# boat_2.net
KiCad netlist of a schematic drawn in EasyEDA Pro
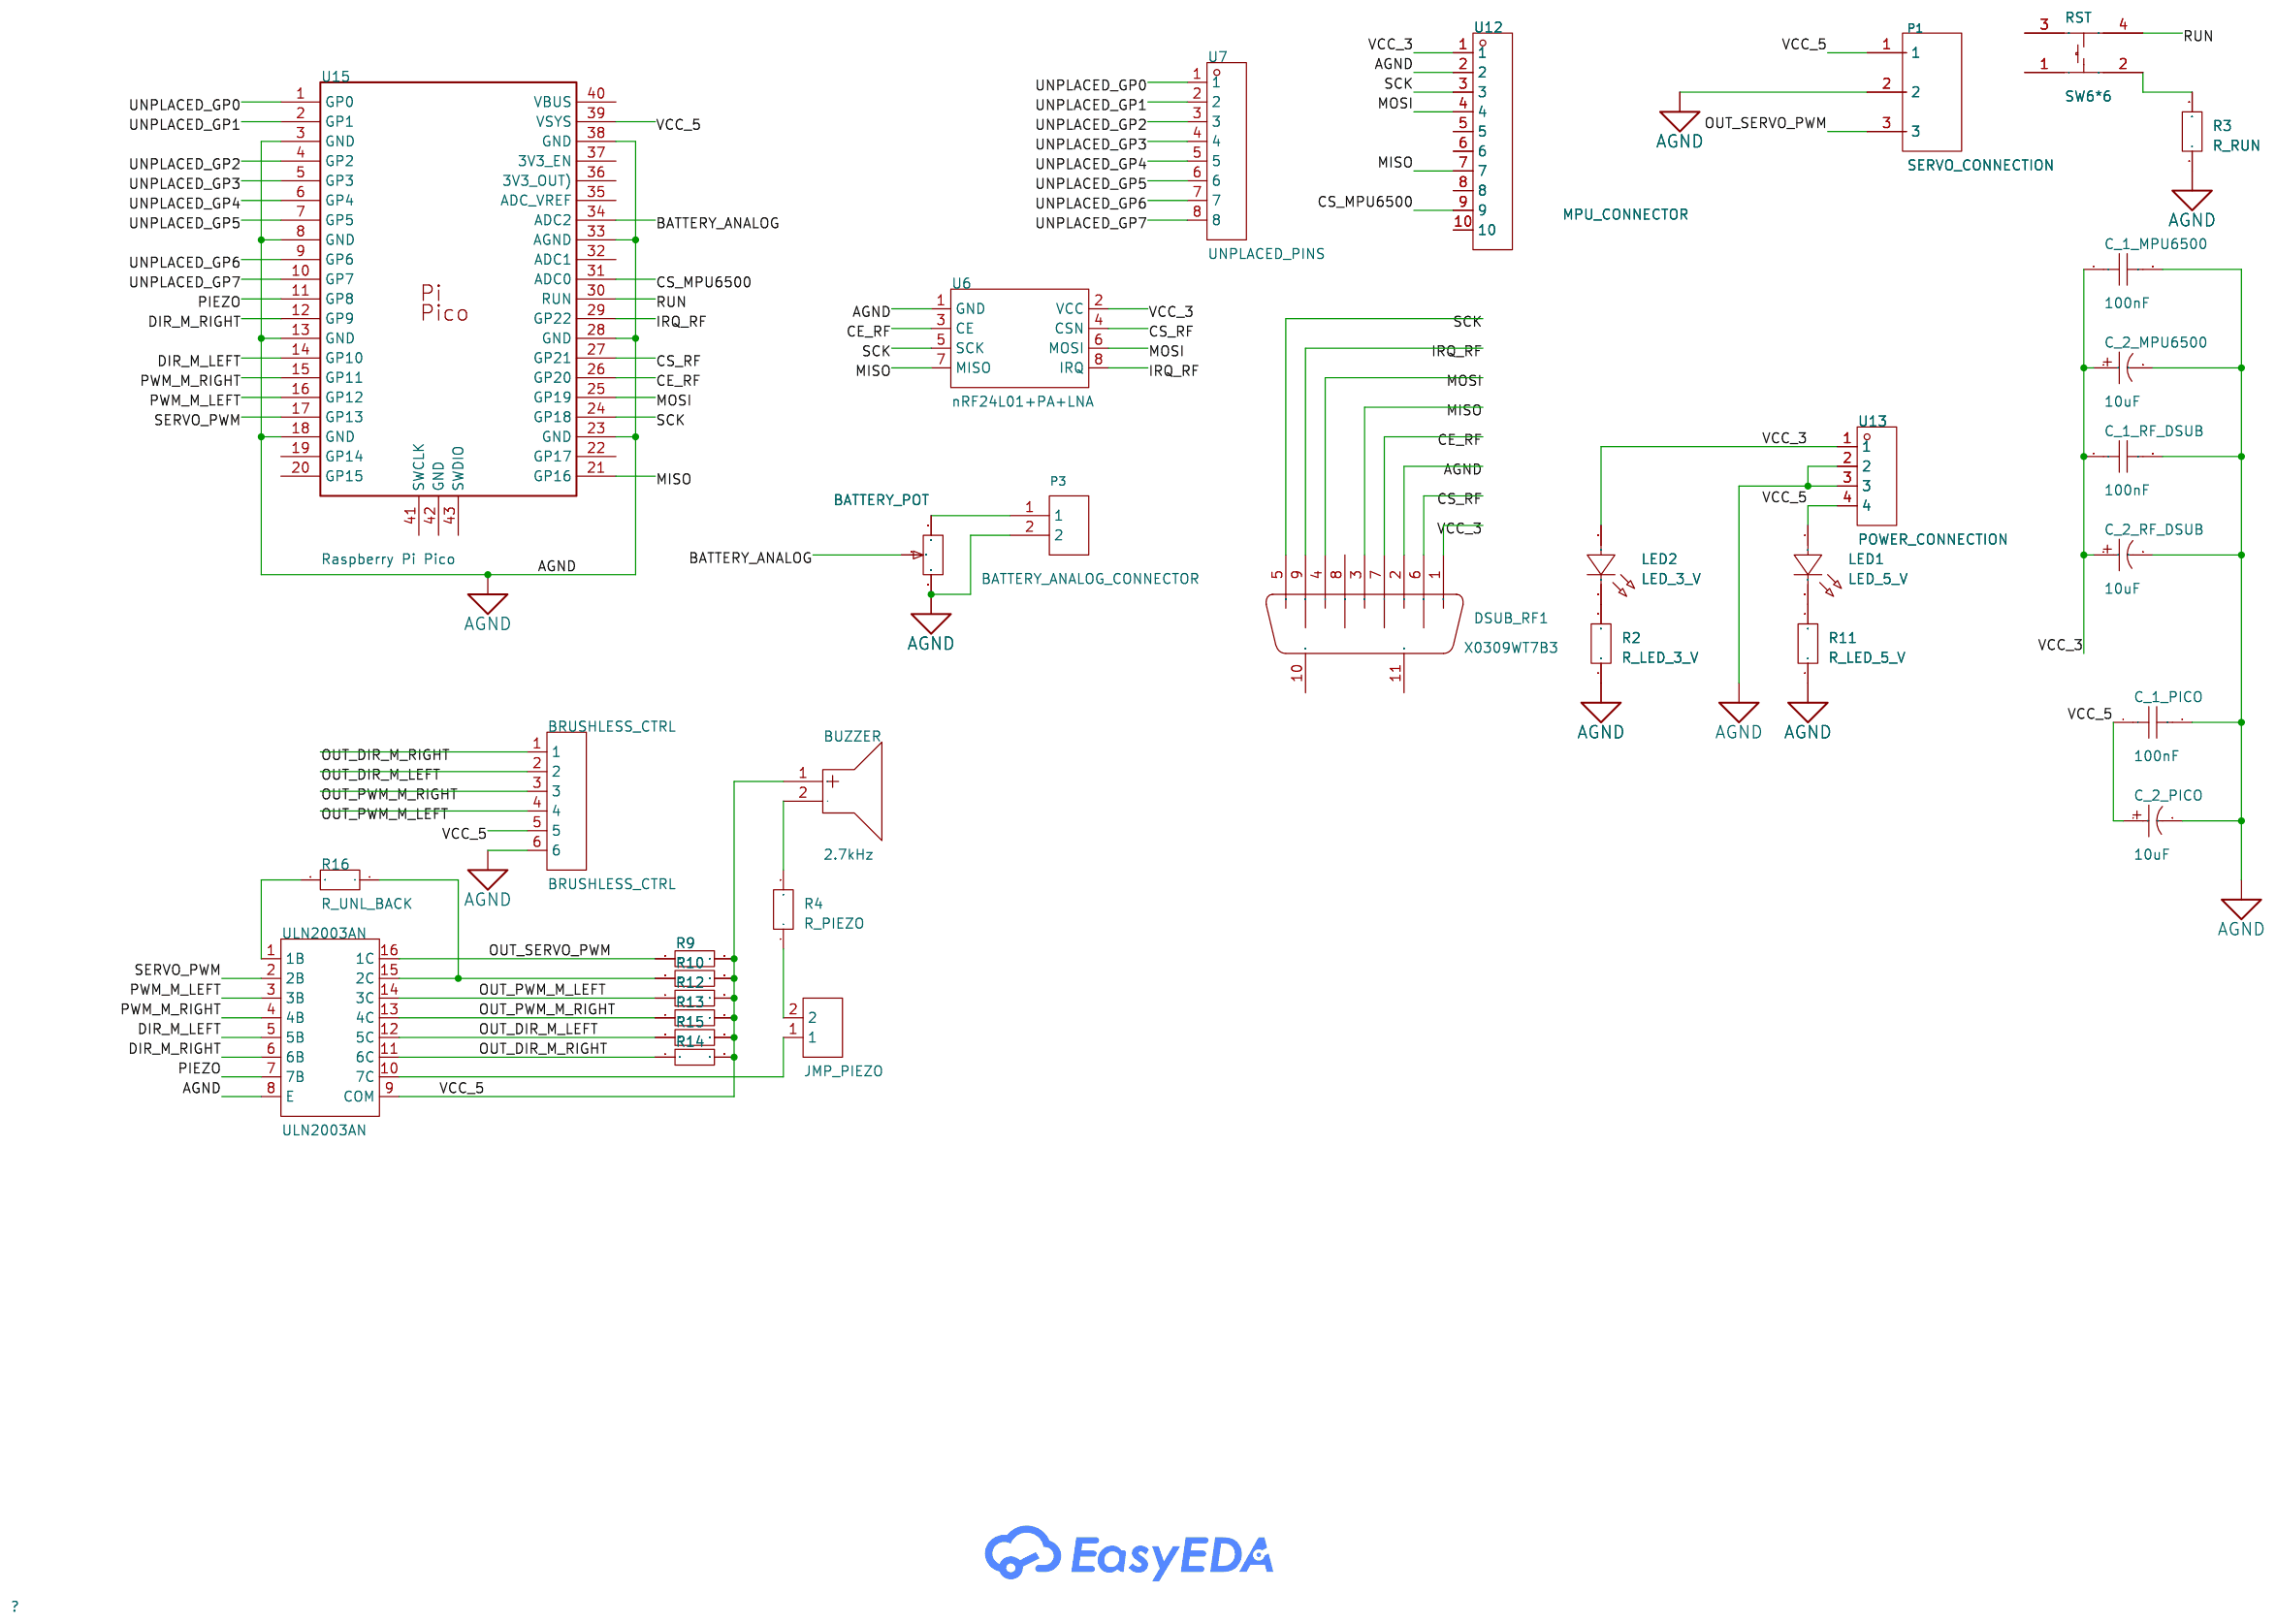
[diagram p0: schematic sheet]

(export (version "E")
  (design (tool "Eeschema 10.0.6"))
  (components
    (comp (ref "BRUSHLESS_CTRL")
      (value "BRUSHLESS_CTRL")
      (footprint "easyedapro:CONN-TH_6P-P2.50_BX-XH2.54-6PZZ")
      (fields (field (name "Manufacturer Part") "BX-XH2.54-6PZZ") (field (name "Manufacturer") "Bossie(博锡)"))
      (libsource (lib "easyedapro") (part "BX-XH2.54-6PZZ"))
    )
    (comp (ref "BUZZER")
      (value "2.7kHz")
      (footprint "easyedapro:BUZ-TH_BD9.0-P5.00-D0.6-FD")
      (fields (field (name "Manufacturer Part") "FMB09A03-3V") (field (name "Manufacturer") "FUET(福声科技)"))
      (libsource (lib "easyedapro") (part "FMB09A03-3V_C417385"))
    )
    (comp (ref "C_1_MPU6500")
      (value "100nF")
      (footprint "easyedapro:CAP-TH_L5.8-W3.6-P5.0-D0.6")
      (fields (field (name "Manufacturer Part") "178MU0002") (field (name "Manufacturer") "KNSCHA(科尼盛)"))
      (libsource (lib "easyedapro") (part "178MU0002"))
    )
    (comp (ref "C_1_PICO")
      (value "100nF")
      (footprint "easyedapro:CAP-TH_L5.8-W3.6-P5.0-D0.6")
      (fields (field (name "Manufacturer Part") "178MU0002") (field (name "Manufacturer") "KNSCHA(科尼盛)"))
      (libsource (lib "easyedapro") (part "178MU0002"))
    )
    (comp (ref "C_1_RF_DSUB")
      (value "100nF")
      (footprint "easyedapro:CAP-TH_L5.8-W3.6-P5.0-D0.6")
      (fields (field (name "Manufacturer Part") "178MU0002") (field (name "Manufacturer") "KNSCHA(科尼盛)"))
      (libsource (lib "easyedapro") (part "178MU0002"))
    )
    (comp (ref "C_2_MPU6500")
      (value "10uF")
      (footprint "easyedapro:CAP-TH_BD8.0-P3.50-D0.6-FD")
      (fields
        (field (name "Manufacturer Part") "35ZLH220MEFC8X11.5")
        (field (name "Manufacturer") "Rubycon(红宝石)")
      )
      (libsource (lib "easyedapro") (part "35ZLH220MEFC8X11.5"))
    )
    (comp (ref "C_2_PICO")
      (value "10uF")
      (footprint "easyedapro:CAP-TH_BD8.0-P3.50-D0.6-FD")
      (fields
        (field (name "Manufacturer Part") "35ZLH220MEFC8X11.5")
        (field (name "Manufacturer") "Rubycon(红宝石)")
      )
      (libsource (lib "easyedapro") (part "35ZLH220MEFC8X11.5"))
    )
    (comp (ref "C_2_RF_DSUB")
      (value "10uF")
      (footprint "easyedapro:CAP-TH_BD8.0-P3.50-D0.6-FD")
      (fields
        (field (name "Manufacturer Part") "35ZLH220MEFC8X11.5")
        (field (name "Manufacturer") "Rubycon(红宝石)")
      )
      (libsource (lib "easyedapro") (part "35ZLH220MEFC8X11.5"))
    )
    (comp (ref "DSUB_RF1")
      (value "X0309WT7B3")
      (footprint "easyedapro:DB9-TH_X0309WT7B3")
      (fields (field (name "Manufacturer") "XKB Connection(中国星坤)"))
      (libsource (lib "easyedapro") (part "X0309WT7B3"))
    )
    (comp (ref "H2")
      (value "JMP_PIEZO")
      (footprint "easyedapro:HDR-TH_2P-P2.54-V-M")
      (fields (field (name "Manufacturer Part") "PZ254V-11-02P") (field (name "Manufacturer") "XFCN(兴飞)"))
      (libsource (lib "easyedapro") (part "PZ254V-11-02P"))
    )
    (comp (ref "LED1")
      (value "LED_5_V")
      (footprint "easyedapro:LED-TH_BD5.5-P2.54_SFH-4545")
      (fields (field (name "Manufacturer Part") "SLR-56MG3F") (field (name "Manufacturer") "ROHM(罗姆)"))
      (libsource (lib "easyedapro") (part "SLR-56MG3F"))
    )
    (comp (ref "LED2")
      (value "LED_3_V")
      (footprint "easyedapro:LED-TH_BD5.5-P2.54_SFH-4545")
      (fields (field (name "Manufacturer Part") "SLR-56MG3F") (field (name "Manufacturer") "ROHM(罗姆)"))
      (libsource (lib "easyedapro") (part "SLR-56MG3F"))
    )
    (comp (ref "P1")
      (value "SERVO_CONNECTION")
      (footprint "easyedapro:CONN-TH_3P-P5.00_WJ126V-5.0-3P")
      (fields
        (field (name "Manufacturer Part") "WJ126V-5.0-3P")
        (field (name "Manufacturer") "KANGNEX(康奈克斯电气)")
      )
      (libsource (lib "easyedapro") (part "WJ126V-5.0-3P"))
    )
    (comp (ref "P3")
      (value "BATTERY_ANALOG_CONNECTOR")
      (footprint "easyedapro:CONN-TH_2P-P5.00_WJ301V-5.00-2P")
      (fields
        (field (name "Manufacturer Part") "WJ301V-5.0-2P")
        (field (name "Manufacturer") "KANGNEX(康奈克斯电气)")
      )
      (libsource (lib "easyedapro") (part "WJ301V-5.0-2P"))
    )
    (comp (ref "R1")
      (value "20kΩ")
      (footprint "easyedapro:RES-ADJ-TH_3296X")
      (fields (field (name "Manufacturer Part") "3296X-203") (field (name "Manufacturer") "BAOTER(宝特)"))
      (libsource (lib "easyedapro") (part "3296X-203"))
    )
    (comp (ref "R2")
      (value "10kΩ")
      (footprint "easyedapro:RES-TH_BD5.0-L15.5-P19.50-D0.7")
      (fields
        (field (name "Manufacturer Part") "MF02SFF1002A10")
        (field (name "Manufacturer") "UNI-ROYAL(厚声)")
      )
      (libsource (lib "easyedapro") (part "MF02SFF1002A10"))
    )
    (comp (ref "R3")
      (value "10kΩ")
      (footprint "easyedapro:RES-TH_BD5.0-L15.5-P19.50-D0.7")
      (fields
        (field (name "Manufacturer Part") "MF02SFF1002A10")
        (field (name "Manufacturer") "UNI-ROYAL(厚声)")
      )
      (libsource (lib "easyedapro") (part "MF02SFF1002A10"))
    )
    (comp (ref "R4")
      (value "10kΩ")
      (footprint "easyedapro:RES-TH_BD5.0-L15.5-P19.50-D0.7")
      (fields
        (field (name "Manufacturer Part") "MF02SFF1002A10")
        (field (name "Manufacturer") "UNI-ROYAL(厚声)")
      )
      (libsource (lib "easyedapro") (part "MF02SFF1002A10"))
    )
    (comp (ref "R9")
      (value "UNL_PULLUP")
      (footprint "easyedapro:R0603")
      (libsource (lib "easyedapro") (part "Res"))
    )
    (comp (ref "R10")
      (value "UNL_PULLUP")
      (footprint "easyedapro:R0603")
      (libsource (lib "easyedapro") (part "Res"))
    )
    (comp (ref "R11")
      (value "10kΩ")
      (footprint "easyedapro:RES-TH_BD5.0-L15.5-P19.50-D0.7")
      (fields
        (field (name "Manufacturer Part") "MF02SFF1002A10")
        (field (name "Manufacturer") "UNI-ROYAL(厚声)")
      )
      (libsource (lib "easyedapro") (part "MF02SFF1002A10"))
    )
    (comp (ref "R12")
      (value "UNL_PULLUP")
      (footprint "easyedapro:R0603")
      (libsource (lib "easyedapro") (part "Res"))
    )
    (comp (ref "R13")
      (value "UNL_PULLUP")
      (footprint "easyedapro:R0603")
      (libsource (lib "easyedapro") (part "Res"))
    )
    (comp (ref "R14")
      (value "UNL_PULLUP")
      (footprint "easyedapro:R0603")
      (libsource (lib "easyedapro") (part "Res"))
    )
    (comp (ref "R15")
      (value "UNL_PULLUP")
      (footprint "easyedapro:R0603")
      (libsource (lib "easyedapro") (part "Res"))
    )
    (comp (ref "R16")
      (value "10kΩ")
      (footprint "easyedapro:RES-TH_BD5.0-L15.5-P19.50-D0.7")
      (fields
        (field (name "Manufacturer Part") "MF02SFF1002A10")
        (field (name "Manufacturer") "UNI-ROYAL(厚声)")
      )
      (libsource (lib "easyedapro") (part "MF02SFF1002A10"))
    )
    (comp (ref "RST")
      (value "SW6*6")
      (footprint "easyedapro:KEY-TH_4P-L6.0-W6.0-P4.5-LS6.5-TL")
      (libsource (lib "easyedapro") (part "SW6*6"))
    )
    (comp (ref "U6")
      (value "nRF24L01+PA+LNA")
      (footprint "easyedapro:COMM-TH_L41.0-W15.5-P2.54_NRF24L01")
      (libsource (lib "easyedapro") (part "NRF24L01+PA+LNA"))
    )
    (comp (ref "U7")
      (value "UNPLACED_PINS")
      (footprint "easyedapro:HDR-TH_8P-P2.54-V-F")
      (fields (field (name "Manufacturer Part") "8Pin排母,间距2.54mm,高5.0mm"))
      (libsource (lib "easyedapro") (part "8PIN排母,间距2.54MM,高5.0MM"))
    )
    (comp (ref "U12")
      (value "MPU_CONNECTOR")
      (footprint "easyedapro:HDR-TH_10P-P2.54-V-F")
      (fields
        (field (name "Manufacturer Part") "PM254-1-10-Z-8.5")
        (field (name "Manufacturer") "HCTL(华灿天禄)")
      )
      (libsource (lib "easyedapro") (part "PM254-1-10-Z-8.5"))
    )
    (comp (ref "U13")
      (value "POWER_CONNECTION")
      (footprint "easyedapro:CONN-TH_DB128V-5.0-4P")
      (fields
        (field (name "Manufacturer Part") "DB128V-5.0-4P-GN-S")
        (field (name "Manufacturer") "DORABO(地博电气)")
      )
      (libsource (lib "easyedapro") (part "DB128V-5.0-4P"))
    )
    (comp (ref "U15")
      (value "Raspberry Pi Pico")
      (fields (field (name "Manufacturer Part") "Pi Pico") (field (name "Manufacturer") "Raspberry Pi"))
      (libsource (lib "easyedapro") (part "Raspberry Pi Pico"))
    )
    (comp (ref "ULN2003AN")
      (value "ULN2003AN")
      (footprint "easyedapro:DIP-16_L19.7-W6.6-P2.54-LS7.6-BL")
      (fields (field (name "Manufacturer") "HGSEMI(华冠)"))
      (libsource (lib "easyedapro") (part "ULN2003AN_C7432319"))
    )
  )
  (nets
    (net (code "1") (name "/BATTERY_ANALOG") (class "Default")
      (node (ref "R1") (pin "2") (pinfunction "2_2") (pintype "input"))
      (node (ref "U15") (pin "34") (pinfunction "ADC2_34") (pintype "unspecified"))
    )
    (net (code "2") (name "/CE_RF") (class "Default")
      (node (ref "DSUB_RF1") (pin "7") (pinfunction "7_7") (pintype "input"))
      (node (ref "U15") (pin "26") (pinfunction "GP20_26") (pintype "unspecified"))
      (node (ref "U6") (pin "3") (pinfunction "CE_3") (pintype "unspecified"))
    )
    (net (code "3") (name "/CS_MPU6500") (class "Default")
      (node (ref "U12") (pin "9") (pinfunction "9_9") (pintype "unspecified"))
      (node (ref "U15") (pin "31") (pinfunction "ADC0_31") (pintype "unspecified"))
    )
    (net (code "4") (name "/CS_RF") (class "Default")
      (node (ref "DSUB_RF1") (pin "6") (pinfunction "6_6") (pintype "input"))
      (node (ref "U15") (pin "27") (pinfunction "GP21_27") (pintype "unspecified"))
      (node (ref "U6") (pin "4") (pinfunction "CSN_4") (pintype "unspecified"))
    )
    (net (code "5") (name "/DIR_M_LEFT") (class "Default")
      (node (ref "U15") (pin "14") (pinfunction "GP10_14") (pintype "unspecified"))
      (node (ref "ULN2003AN") (pin "5") (pinfunction "5B_5") (pintype "unspecified"))
    )
    (net (code "6") (name "/DIR_M_RIGHT") (class "Default")
      (node (ref "U15") (pin "12") (pinfunction "GP9_12") (pintype "unspecified"))
      (node (ref "ULN2003AN") (pin "6") (pinfunction "6B_6") (pintype "unspecified"))
    )
    (net (code "7") (name "/IRQ_RF") (class "Default")
      (node (ref "DSUB_RF1") (pin "9") (pinfunction "9_9") (pintype "input"))
      (node (ref "U15") (pin "29") (pinfunction "GP22_29") (pintype "unspecified"))
      (node (ref "U6") (pin "8") (pinfunction "IRQ_8") (pintype "unspecified"))
    )
    (net (code "8") (name "/MISO") (class "Default")
      (node (ref "DSUB_RF1") (pin "3") (pinfunction "3_3") (pintype "input"))
      (node (ref "U12") (pin "7") (pinfunction "7_7") (pintype "unspecified"))
      (node (ref "U15") (pin "21") (pinfunction "GP16_21") (pintype "unspecified"))
      (node (ref "U6") (pin "7") (pinfunction "MISO_7") (pintype "unspecified"))
    )
    (net (code "9") (name "/MOSI") (class "Default")
      (node (ref "DSUB_RF1") (pin "4") (pinfunction "4_4") (pintype "input"))
      (node (ref "U12") (pin "4") (pinfunction "4_4") (pintype "unspecified"))
      (node (ref "U15") (pin "25") (pinfunction "GP19_25") (pintype "unspecified"))
      (node (ref "U6") (pin "6") (pinfunction "MOSI_6") (pintype "unspecified"))
    )
    (net (code "10") (name "/OUT_DIR_M_LEFT") (class "Default")
      (node (ref "BRUSHLESS_CTRL") (pin "2") (pinfunction "2_2") (pintype "unspecified"))
      (node (ref "R15") (pin "1") (pinfunction "1_1") (pintype "input"))
      (node (ref "ULN2003AN") (pin "12") (pinfunction "5C_12") (pintype "unspecified"))
    )
    (net (code "11") (name "/OUT_DIR_M_RIGHT") (class "Default")
      (node (ref "BRUSHLESS_CTRL") (pin "1") (pinfunction "1_1") (pintype "unspecified"))
      (node (ref "R14") (pin "1") (pinfunction "1_1") (pintype "input"))
      (node (ref "ULN2003AN") (pin "11") (pinfunction "6C_11") (pintype "unspecified"))
    )
    (net (code "12") (name "/OUT_PWM_M_LEFT") (class "Default")
      (node (ref "BRUSHLESS_CTRL") (pin "4") (pinfunction "4_4") (pintype "unspecified"))
      (node (ref "R12") (pin "1") (pinfunction "1_1") (pintype "input"))
      (node (ref "ULN2003AN") (pin "14") (pinfunction "3C_14") (pintype "unspecified"))
    )
    (net (code "13") (name "/OUT_PWM_M_RIGHT") (class "Default")
      (node (ref "BRUSHLESS_CTRL") (pin "3") (pinfunction "3_3") (pintype "unspecified"))
      (node (ref "R13") (pin "1") (pinfunction "1_1") (pintype "input"))
      (node (ref "ULN2003AN") (pin "13") (pinfunction "4C_13") (pintype "unspecified"))
    )
    (net (code "14") (name "/OUT_SERVO_PWM") (class "Default")
      (node (ref "P1") (pin "3") (pinfunction "3_3") (pintype "input"))
      (node (ref "R9") (pin "1") (pinfunction "1_1") (pintype "input"))
      (node (ref "ULN2003AN") (pin "16") (pinfunction "1C_16") (pintype "unspecified"))
    )
    (net (code "15") (name "/PIEZO") (class "Default")
      (node (ref "U15") (pin "11") (pinfunction "GP8_11") (pintype "unspecified"))
      (node (ref "ULN2003AN") (pin "7") (pinfunction "7B_7") (pintype "unspecified"))
    )
    (net (code "16") (name "/PWM_M_LEFT") (class "Default")
      (node (ref "U15") (pin "16") (pinfunction "GP12_16") (pintype "unspecified"))
      (node (ref "ULN2003AN") (pin "3") (pinfunction "3B_3") (pintype "unspecified"))
    )
    (net (code "17") (name "/PWM_M_RIGHT") (class "Default")
      (node (ref "U15") (pin "15") (pinfunction "GP11_15") (pintype "unspecified"))
      (node (ref "ULN2003AN") (pin "4") (pinfunction "4B_4") (pintype "unspecified"))
    )
    (net (code "18") (name "/RUN") (class "Default")
      (node (ref "RST") (pin "4") (pinfunction "4_4") (pintype "unspecified"))
      (node (ref "U15") (pin "30") (pinfunction "RUN_30") (pintype "unspecified"))
    )
    (net (code "19") (name "/SCK") (class "Default")
      (node (ref "DSUB_RF1") (pin "5") (pinfunction "5_5") (pintype "input"))
      (node (ref "U12") (pin "3") (pinfunction "3_3") (pintype "unspecified"))
      (node (ref "U15") (pin "24") (pinfunction "GP18_24") (pintype "unspecified"))
      (node (ref "U6") (pin "5") (pinfunction "SCK_5") (pintype "unspecified"))
    )
    (net (code "20") (name "/SERVO_PWM") (class "Default")
      (node (ref "U15") (pin "17") (pinfunction "GP13_17") (pintype "unspecified"))
      (node (ref "ULN2003AN") (pin "2") (pinfunction "2B_2") (pintype "unspecified"))
    )
    (net (code "21") (name "/UNPLACED_GP0") (class "Default")
      (node (ref "U15") (pin "1") (pinfunction "GP0_1") (pintype "unspecified"))
      (node (ref "U7") (pin "1") (pinfunction "1_1") (pintype "unspecified"))
    )
    (net (code "22") (name "/UNPLACED_GP1") (class "Default")
      (node (ref "U15") (pin "2") (pinfunction "GP1_2") (pintype "unspecified"))
      (node (ref "U7") (pin "2") (pinfunction "2_2") (pintype "unspecified"))
    )
    (net (code "23") (name "/UNPLACED_GP2") (class "Default")
      (node (ref "U15") (pin "4") (pinfunction "GP2_4") (pintype "unspecified"))
      (node (ref "U7") (pin "3") (pinfunction "3_3") (pintype "unspecified"))
    )
    (net (code "24") (name "/UNPLACED_GP3") (class "Default")
      (node (ref "U15") (pin "5") (pinfunction "GP3_5") (pintype "unspecified"))
      (node (ref "U7") (pin "4") (pinfunction "4_4") (pintype "unspecified"))
    )
    (net (code "25") (name "/UNPLACED_GP4") (class "Default")
      (node (ref "U15") (pin "6") (pinfunction "GP4_6") (pintype "unspecified"))
      (node (ref "U7") (pin "5") (pinfunction "5_5") (pintype "unspecified"))
    )
    (net (code "26") (name "/UNPLACED_GP5") (class "Default")
      (node (ref "U15") (pin "7") (pinfunction "GP5_7") (pintype "unspecified"))
      (node (ref "U7") (pin "6") (pinfunction "6_6") (pintype "unspecified"))
    )
    (net (code "27") (name "/UNPLACED_GP6") (class "Default")
      (node (ref "U15") (pin "9") (pinfunction "GP6_9") (pintype "unspecified"))
      (node (ref "U7") (pin "7") (pinfunction "7_7") (pintype "unspecified"))
    )
    (net (code "28") (name "/UNPLACED_GP7") (class "Default")
      (node (ref "U15") (pin "10") (pinfunction "GP7_10") (pintype "unspecified"))
      (node (ref "U7") (pin "8") (pinfunction "8_8") (pintype "unspecified"))
    )
    (net (code "29") (name "/VCC_3") (class "Default")
      (node (ref "C_1_MPU6500") (pin "1") (pinfunction "1_1") (pintype "unspecified"))
      (node (ref "C_1_RF_DSUB") (pin "1") (pinfunction "1_1") (pintype "unspecified"))
      (node (ref "C_2_MPU6500") (pin "1") (pinfunction "1_1") (pintype "input"))
      (node (ref "C_2_RF_DSUB") (pin "1") (pinfunction "1_1") (pintype "input"))
      (node (ref "DSUB_RF1") (pin "1") (pinfunction "1_1") (pintype "input"))
      (node (ref "LED2") (pin "1") (pinfunction "A_1") (pintype "unspecified"))
      (node (ref "U12") (pin "1") (pinfunction "1_1") (pintype "unspecified"))
      (node (ref "U13") (pin "1") (pinfunction "1_1") (pintype "unspecified"))
      (node (ref "U6") (pin "2") (pinfunction "VCC_2") (pintype "unspecified"))
    )
    (net (code "30") (name "/VCC_5") (class "Default")
      (node (ref "BRUSHLESS_CTRL") (pin "5") (pinfunction "5_5") (pintype "unspecified"))
      (node (ref "BUZZER") (pin "1") (pinfunction "+_1") (pintype "unspecified"))
      (node (ref "C_1_PICO") (pin "1") (pinfunction "1_1") (pintype "unspecified"))
      (node (ref "C_2_PICO") (pin "1") (pinfunction "1_1") (pintype "input"))
      (node (ref "LED1") (pin "1") (pinfunction "A_1") (pintype "unspecified"))
      (node (ref "P1") (pin "1") (pinfunction "1_1") (pintype "input"))
      (node (ref "R10") (pin "2") (pinfunction "2_2") (pintype "input"))
      (node (ref "R12") (pin "2") (pinfunction "2_2") (pintype "input"))
      (node (ref "R13") (pin "2") (pinfunction "2_2") (pintype "input"))
      (node (ref "R14") (pin "2") (pinfunction "2_2") (pintype "input"))
      (node (ref "R15") (pin "2") (pinfunction "2_2") (pintype "input"))
      (node (ref "R9") (pin "2") (pinfunction "2_2") (pintype "input"))
      (node (ref "U13") (pin "4") (pinfunction "4_4") (pintype "unspecified"))
      (node (ref "U15") (pin "39") (pinfunction "VSYS_39") (pintype "unspecified"))
      (node (ref "ULN2003AN") (pin "9") (pinfunction "COM_9") (pintype "unspecified"))
    )
    (net (code "31") (name "AGND") (class "Default")
      (node (ref "BRUSHLESS_CTRL") (pin "6") (pinfunction "6_6") (pintype "unspecified"))
      (node (ref "C_1_MPU6500") (pin "2") (pinfunction "2_2") (pintype "unspecified"))
      (node (ref "C_1_PICO") (pin "2") (pinfunction "2_2") (pintype "unspecified"))
      (node (ref "C_1_RF_DSUB") (pin "2") (pinfunction "2_2") (pintype "unspecified"))
      (node (ref "C_2_MPU6500") (pin "2") (pinfunction "2_2") (pintype "input"))
      (node (ref "C_2_PICO") (pin "2") (pinfunction "2_2") (pintype "input"))
      (node (ref "C_2_RF_DSUB") (pin "2") (pinfunction "2_2") (pintype "input"))
      (node (ref "DSUB_RF1") (pin "2") (pinfunction "2_2") (pintype "input"))
      (node (ref "P1") (pin "2") (pinfunction "2_2") (pintype "input"))
      (node (ref "P3") (pin "2") (pinfunction "2_2") (pintype "input"))
      (node (ref "R1") (pin "3") (pinfunction "3_3") (pintype "input"))
      (node (ref "R11") (pin "1") (pinfunction "1_1") (pintype "unspecified"))
      (node (ref "R2") (pin "1") (pinfunction "1_1") (pintype "unspecified"))
      (node (ref "R3") (pin "1") (pinfunction "1_1") (pintype "unspecified"))
      (node (ref "U12") (pin "2") (pinfunction "2_2") (pintype "unspecified"))
      (node (ref "U13") (pin "2") (pinfunction "2_2") (pintype "unspecified"))
      (node (ref "U13") (pin "3") (pinfunction "3_3") (pintype "unspecified"))
      (node (ref "U15") (pin "13") (pinfunction "GND_13") (pintype "unspecified"))
      (node (ref "U15") (pin "18") (pinfunction "GND_18") (pintype "unspecified"))
      (node (ref "U15") (pin "23") (pinfunction "GND_23") (pintype "unspecified"))
      (node (ref "U15") (pin "28") (pinfunction "GND_28") (pintype "unspecified"))
      (node (ref "U15") (pin "3") (pinfunction "GND_3") (pintype "unspecified"))
      (node (ref "U15") (pin "33") (pinfunction "AGND_33") (pintype "unspecified"))
      (node (ref "U15") (pin "38") (pinfunction "GND_38") (pintype "unspecified"))
      (node (ref "U15") (pin "8") (pinfunction "GND_8") (pintype "unspecified"))
      (node (ref "U6") (pin "1") (pinfunction "GND_1") (pintype "unspecified"))
      (node (ref "ULN2003AN") (pin "8") (pinfunction "E_8") (pintype "unspecified"))
    )
    (net (code "32") (name "Net-(BUZZER--)") (class "Default")
      (node (ref "BUZZER") (pin "2") (pinfunction "-_2") (pintype "unspecified"))
      (node (ref "R4") (pin "2") (pinfunction "2_2") (pintype "unspecified"))
    )
    (net (code "33") (name "Net-(H2-Pad2)") (class "Default")
      (node (ref "H2") (pin "2") (pinfunction "2_2") (pintype "unspecified"))
      (node (ref "R4") (pin "1") (pinfunction "1_1") (pintype "unspecified"))
    )
    (net (code "34") (name "Net-(LED1-K)") (class "Default")
      (node (ref "LED1") (pin "2") (pinfunction "K_2") (pintype "unspecified"))
      (node (ref "R11") (pin "2") (pinfunction "2_2") (pintype "unspecified"))
    )
    (net (code "35") (name "Net-(LED2-K)") (class "Default")
      (node (ref "LED2") (pin "2") (pinfunction "K_2") (pintype "unspecified"))
      (node (ref "R2") (pin "2") (pinfunction "2_2") (pintype "unspecified"))
    )
    (net (code "36") (name "Net-(P3-Pad1)") (class "Default")
      (node (ref "P3") (pin "1") (pinfunction "1_1") (pintype "input"))
      (node (ref "R1") (pin "1") (pinfunction "1_1") (pintype "input"))
    )
    (net (code "37") (name "Net-(R3-Pad2)") (class "Default")
      (node (ref "R3") (pin "2") (pinfunction "2_2") (pintype "unspecified"))
      (node (ref "RST") (pin "2") (pinfunction "2_2") (pintype "unspecified"))
    )
    (net (code "38") (name "Net-(ULN2003AN-1B)") (class "Default")
      (node (ref "R16") (pin "2") (pinfunction "2_2") (pintype "unspecified"))
      (node (ref "ULN2003AN") (pin "1") (pinfunction "1B_1") (pintype "unspecified"))
    )
    (net (code "39") (name "Net-(ULN2003AN-2C)") (class "Default")
      (node (ref "R10") (pin "1") (pinfunction "1_1") (pintype "input"))
      (node (ref "R16") (pin "1") (pinfunction "1_1") (pintype "unspecified"))
      (node (ref "ULN2003AN") (pin "15") (pinfunction "2C_15") (pintype "unspecified"))
    )
    (net (code "40") (name "Net-(ULN2003AN-7C)") (class "Default")
      (node (ref "H2") (pin "1") (pinfunction "1_1") (pintype "unspecified"))
      (node (ref "ULN2003AN") (pin "10") (pinfunction "7C_10") (pintype "unspecified"))
    )
    (net (code "41") (name "unconnected-(DSUB_RF1-MH1-Pad10)") (class "Default")
      (node (ref "DSUB_RF1") (pin "10") (pinfunction "MH1_10") (pintype "input"))
    )
    (net (code "42") (name "unconnected-(DSUB_RF1-MH2-Pad11)") (class "Default")
      (node (ref "DSUB_RF1") (pin "11") (pinfunction "MH2_11") (pintype "input"))
    )
    (net (code "43") (name "unconnected-(DSUB_RF1-Pad8)") (class "Default")
      (node (ref "DSUB_RF1") (pin "8") (pinfunction "8_8") (pintype "input"))
    )
    (net (code "44") (name "unconnected-(RST-Pad1)") (class "Default")
      (node (ref "RST") (pin "1") (pinfunction "1_1") (pintype "unspecified"))
    )
    (net (code "45") (name "unconnected-(RST-Pad3)") (class "Default")
      (node (ref "RST") (pin "3") (pinfunction "3_3") (pintype "unspecified"))
    )
    (net (code "46") (name "unconnected-(U12-Pad5)") (class "Default")
      (node (ref "U12") (pin "5") (pinfunction "5_5") (pintype "unspecified"))
    )
    (net (code "47") (name "unconnected-(U12-Pad6)") (class "Default")
      (node (ref "U12") (pin "6") (pinfunction "6_6") (pintype "unspecified"))
    )
    (net (code "48") (name "unconnected-(U12-Pad8)") (class "Default")
      (node (ref "U12") (pin "8") (pinfunction "8_8") (pintype "unspecified"))
    )
    (net (code "49") (name "unconnected-(U12-Pad10)") (class "Default")
      (node (ref "U12") (pin "10") (pinfunction "10_10") (pintype "unspecified"))
    )
    (net (code "50") (name "unconnected-(U15-3V3_EN-Pad37)") (class "Default")
      (node (ref "U15") (pin "37") (pinfunction "3V3_EN_37") (pintype "unspecified"))
    )
    (net (code "51") (name "unconnected-(U15-3V3_OUT)-Pad36)") (class "Default")
      (node (ref "U15") (pin "36") (pinfunction "3V3_OUT)_36") (pintype "unspecified"))
    )
    (net (code "52") (name "unconnected-(U15-ADC1-Pad32)") (class "Default")
      (node (ref "U15") (pin "32") (pinfunction "ADC1_32") (pintype "unspecified"))
    )
    (net (code "53") (name "unconnected-(U15-ADC_VREF-Pad35)") (class "Default")
      (node (ref "U15") (pin "35") (pinfunction "ADC_VREF_35") (pintype "unspecified"))
    )
    (net (code "54") (name "unconnected-(U15-GND-Pad42)") (class "Default")
      (node (ref "U15") (pin "42") (pinfunction "GND_42") (pintype "unspecified"))
    )
    (net (code "55") (name "unconnected-(U15-GP14-Pad19)") (class "Default")
      (node (ref "U15") (pin "19") (pinfunction "GP14_19") (pintype "unspecified"))
    )
    (net (code "56") (name "unconnected-(U15-GP15-Pad20)") (class "Default")
      (node (ref "U15") (pin "20") (pinfunction "GP15_20") (pintype "unspecified"))
    )
    (net (code "57") (name "unconnected-(U15-GP17-Pad22)") (class "Default")
      (node (ref "U15") (pin "22") (pinfunction "GP17_22") (pintype "unspecified"))
    )
    (net (code "58") (name "unconnected-(U15-SWCLK-Pad41)") (class "Default")
      (node (ref "U15") (pin "41") (pinfunction "SWCLK_41") (pintype "unspecified"))
    )
    (net (code "59") (name "unconnected-(U15-SWDIO-Pad43)") (class "Default")
      (node (ref "U15") (pin "43") (pinfunction "SWDIO_43") (pintype "unspecified"))
    )
    (net (code "60") (name "unconnected-(U15-VBUS-Pad40)") (class "Default")
      (node (ref "U15") (pin "40") (pinfunction "VBUS_40") (pintype "unspecified"))
    )
  )
)
